# mightywatt.net
KiCad netlist of a schematic drawn in EAGLE
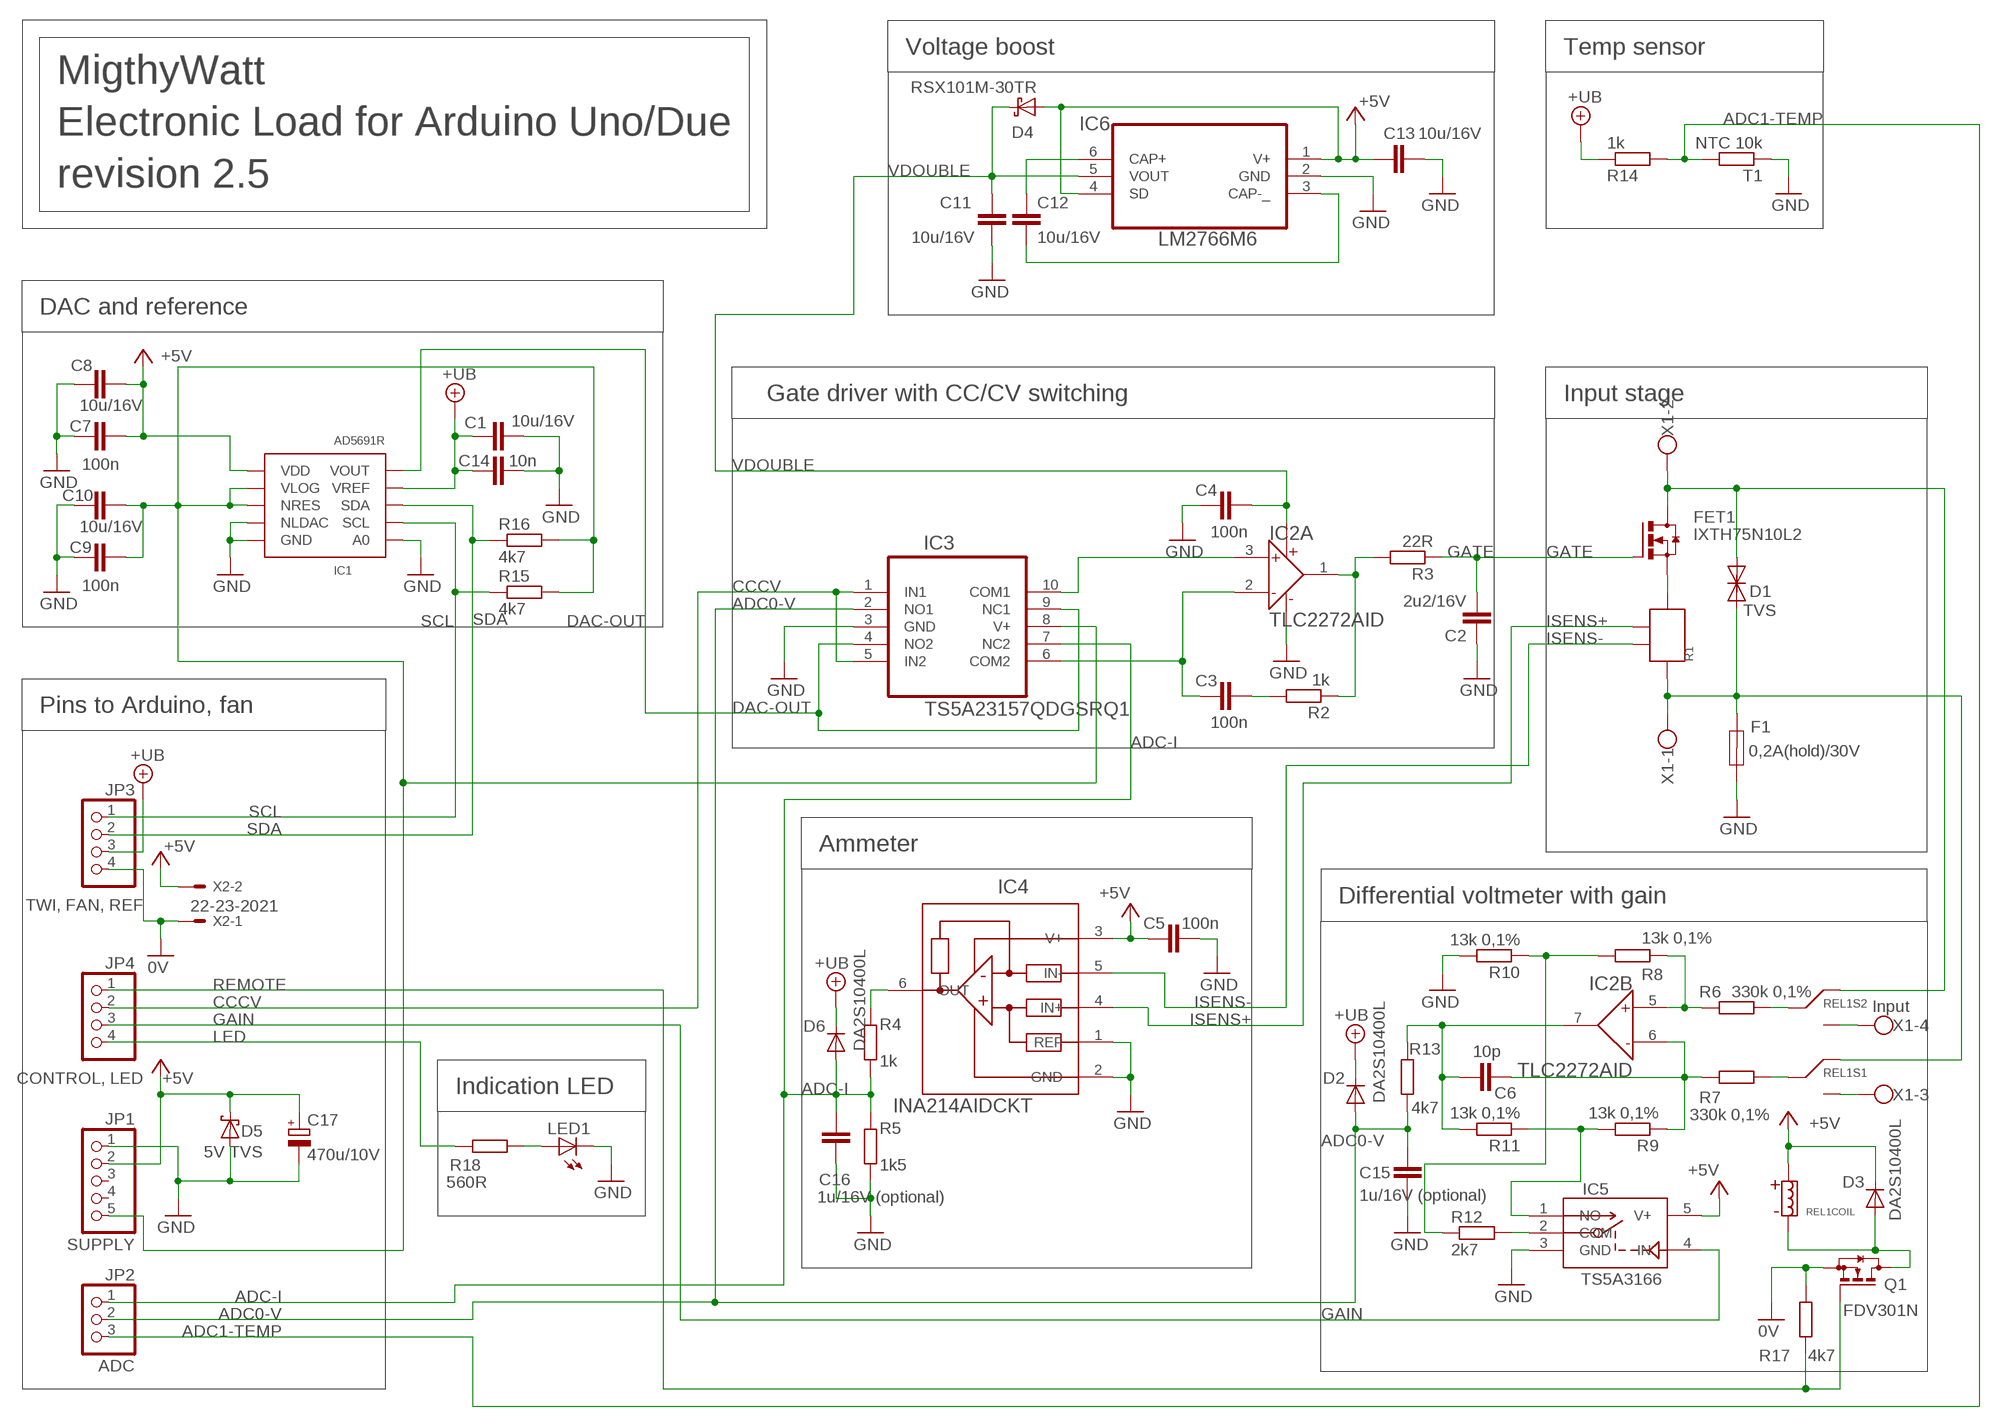
[diagram p0: schematic, sheet 1]

(export (version "E")
  (design (tool "Eeschema 10.0.6"))
  (components
    (comp (ref "C1")
      (value "10u/16V")
      (footprint "eagle-import:C1206")
      (libsource (lib "eagle-import") (part "C-EUC1206"))
    )
    (comp (ref "C2")
      (value "2u2/16V")
      (footprint "eagle-import:C1206")
      (libsource (lib "eagle-import") (part "C-EUC1206"))
    )
    (comp (ref "C3")
      (value "100n")
      (footprint "eagle-import:C0603")
      (libsource (lib "eagle-import") (part "C-EUC0603"))
    )
    (comp (ref "C4")
      (value "100n")
      (footprint "eagle-import:C0603")
      (libsource (lib "eagle-import") (part "C-EUC0603"))
    )
    (comp (ref "C5")
      (value "100n")
      (footprint "eagle-import:C0603")
      (libsource (lib "eagle-import") (part "C-EUC0603"))
    )
    (comp (ref "C6")
      (value "10p")
      (footprint "eagle-import:C0603")
      (libsource (lib "eagle-import") (part "C-EUC0603"))
    )
    (comp (ref "C7")
      (value "100n")
      (footprint "eagle-import:C0603")
      (libsource (lib "eagle-import") (part "C-EUC0603"))
    )
    (comp (ref "C8")
      (value "10u/16V")
      (footprint "eagle-import:C1206")
      (libsource (lib "eagle-import") (part "C-EUC1206"))
    )
    (comp (ref "C9")
      (value "100n")
      (footprint "eagle-import:C0603")
      (libsource (lib "eagle-import") (part "C-EUC0603"))
    )
    (comp (ref "C10")
      (value "10u/16V")
      (footprint "eagle-import:C1206")
      (libsource (lib "eagle-import") (part "C-EUC1206"))
    )
    (comp (ref "C11")
      (value "10u/16V")
      (footprint "eagle-import:C1206")
      (libsource (lib "eagle-import") (part "C-EUC1206"))
    )
    (comp (ref "C12")
      (value "10u/16V")
      (footprint "eagle-import:C1206")
      (libsource (lib "eagle-import") (part "C-EUC1206"))
    )
    (comp (ref "C13")
      (value "10u/16V")
      (footprint "eagle-import:C1206")
      (libsource (lib "eagle-import") (part "C-EUC1206"))
    )
    (comp (ref "C14")
      (value "10n")
      (footprint "eagle-import:C0805")
      (libsource (lib "eagle-import") (part "C-EUC0805"))
    )
    (comp (ref "C15")
      (value "1u/16V (optional)")
      (footprint "eagle-import:C0603")
      (libsource (lib "eagle-import") (part "C-EUC0603"))
    )
    (comp (ref "C16")
      (value "1u/16V (optional)")
      (footprint "eagle-import:C0603")
      (libsource (lib "eagle-import") (part "C-EUC0603"))
    )
    (comp (ref "C17")
      (value "470u/10V")
      (footprint "eagle-import:SMC_E")
      (libsource (lib "eagle-import") (part "CPOL-EUSMCE"))
    )
    (comp (ref "D1")
      (value "TVS")
      (footprint "eagle-import:SMC")
      (libsource (lib "eagle-import") (part "diode-tvs_DIODE-SMC"))
    )
    (comp (ref "D2")
      (value "DA2S10400L")
      (footprint "eagle-import:SOD523")
      (libsource (lib "eagle-import") (part "DIODE-SOD523"))
    )
    (comp (ref "D3")
      (value "DA2S10400L")
      (footprint "eagle-import:SOD523")
      (libsource (lib "eagle-import") (part "DIODE-SOD523"))
    )
    (comp (ref "D4")
      (value "RSX101M-30TR")
      (footprint "eagle-import:SOD123")
      (libsource (lib "eagle-import") (part "diode-schottky_DIODE-SOD123"))
    )
    (comp (ref "D5")
      (value "5V TVS")
      (footprint "eagle-import:SMB")
      (libsource (lib "eagle-import") (part "SCHOTTKY-DIODESMD"))
    )
    (comp (ref "D6")
      (value "DA2S10400L")
      (footprint "eagle-import:SOD523")
      (libsource (lib "eagle-import") (part "DIODE-SOD523"))
    )
    (comp (ref "F1")
      (value "0,2A(hold)/30V")
      (footprint "eagle-import:R1812")
      (fields (field (name "MPN") "1812L050PR"))
      (libsource (lib "eagle-import") (part "LITTELFUSE_1812_500MA"))
    )
    (comp (ref "FET1")
      (value "IXTH75N10L2")
      (footprint "eagle-import:TO-247AD-H")
      (libsource (lib "eagle-import") (part "IXTH75N10L2"))
    )
    (comp (ref "IC1")
      (value "AD5691RAD5691R")
      (footprint "eagle-import:SOP50P490X110-10N")
      (libsource (lib "eagle-import") (part "AD5691RAD5691R"))
    )
    (comp (ref "IC2")
      (value "TLC2272AID")
      (footprint "eagle-import:SOIC127P600X175-8N")
      (libsource (lib "eagle-import") (part "TLC2272AID"))
    )
    (comp (ref "IC3")
      (value "TS5A23157QDGSRQ1")
      (footprint "eagle-import:SOP50P490X110-10N")
      (fields (field (name "MPN") "TS5A23157QDGSRQ1 "))
      (libsource (lib "eagle-import") (part "TS5A23157QDGSRQ1"))
    )
    (comp (ref "IC4")
      (value "INA214AIDCKT")
      (footprint "eagle-import:SOT65P210X110-6N")
      (fields (field (name "MPN") "INA214BIDCKT"))
      (libsource (lib "eagle-import") (part "INA214AIDCKT"))
    )
    (comp (ref "IC5")
      (value "TS5A3166")
      (footprint "eagle-import:SC70-5")
      (libsource (lib "eagle-import") (part "TS5A3166"))
    )
    (comp (ref "IC6")
      (value "LM2766M6")
      (footprint "eagle-import:SOT95P285X122-6N")
      (libsource (lib "eagle-import") (part "LM2766M6"))
    )
    (comp (ref "JP1")
      (value "SUPPLY")
      (footprint "eagle-import:1X05")
      (libsource (lib "eagle-import") (part "PINHD-1X5"))
    )
    (comp (ref "JP2")
      (value "ADC")
      (footprint "eagle-import:1X03")
      (libsource (lib "eagle-import") (part "PINHD-1X3"))
    )
    (comp (ref "JP3")
      (value "TWI, FAN, REF")
      (footprint "eagle-import:1X04")
      (libsource (lib "eagle-import") (part "PINHD-1X4"))
    )
    (comp (ref "JP4")
      (value "CONTROL, LED")
      (footprint "eagle-import:1X04")
      (libsource (lib "eagle-import") (part "PINHD-1X4"))
    )
    (comp (ref "LED1")
      (value "LEDCHIP-LED0805")
      (footprint "eagle-import:CHIP-LED0805")
      (libsource (lib "eagle-import") (part "LEDCHIP-LED0805"))
    )
    (comp (ref "Q1")
      (value "BSS123")
      (footprint "eagle-import:SOT23")
      (fields (field (name "PARTNAME") "FDV301N"))
      (libsource (lib "eagle-import") (part "BSS123"))
    )
    (comp (ref "R1")
      (value "WSL3637")
      (footprint "eagle-import:POWER-R-4TERM")
      (libsource (lib "eagle-import") (part "WSL3637"))
    )
    (comp (ref "R2")
      (value "1k")
      (footprint "eagle-import:R0603")
      (libsource (lib "eagle-import") (part "R-EU_R0603"))
    )
    (comp (ref "R3")
      (value "22R")
      (footprint "eagle-import:R0603")
      (libsource (lib "eagle-import") (part "R-EU_R0603"))
    )
    (comp (ref "R4")
      (value "1k")
      (footprint "eagle-import:R0603")
      (libsource (lib "eagle-import") (part "R-EU_R0603"))
    )
    (comp (ref "R5")
      (value "1k5")
      (footprint "eagle-import:R0603")
      (libsource (lib "eagle-import") (part "R-EU_R0603"))
    )
    (comp (ref "R6")
      (value "330k 0,1%")
      (footprint "eagle-import:R0603")
      (libsource (lib "eagle-import") (part "R-EU_R0603"))
    )
    (comp (ref "R7")
      (value "330k 0,1%")
      (footprint "eagle-import:R0603")
      (libsource (lib "eagle-import") (part "R-EU_R0603"))
    )
    (comp (ref "R8")
      (value "13k 0,1%")
      (footprint "eagle-import:R0603")
      (libsource (lib "eagle-import") (part "R-EU_R0603"))
    )
    (comp (ref "R9")
      (value "13k 0,1%")
      (footprint "eagle-import:R0603")
      (libsource (lib "eagle-import") (part "R-EU_R0603"))
    )
    (comp (ref "R10")
      (value "13k 0,1%")
      (footprint "eagle-import:R0603")
      (libsource (lib "eagle-import") (part "R-EU_R0603"))
    )
    (comp (ref "R11")
      (value "13k 0,1%")
      (footprint "eagle-import:R0603")
      (libsource (lib "eagle-import") (part "R-EU_R0603"))
    )
    (comp (ref "R12")
      (value "2k7")
      (footprint "eagle-import:R0603")
      (libsource (lib "eagle-import") (part "R-EU_R0603"))
    )
    (comp (ref "R13")
      (value "4k7")
      (footprint "eagle-import:R0603")
      (libsource (lib "eagle-import") (part "R-EU_R0603"))
    )
    (comp (ref "R14")
      (value "1k")
      (footprint "eagle-import:R0603")
      (libsource (lib "eagle-import") (part "R-EU_R0603"))
    )
    (comp (ref "R15")
      (value "4k7")
      (footprint "eagle-import:R0603")
      (libsource (lib "eagle-import") (part "R-EU_R0603"))
    )
    (comp (ref "R16")
      (value "4k7")
      (footprint "eagle-import:R0603")
      (libsource (lib "eagle-import") (part "R-EU_R0603"))
    )
    (comp (ref "R17")
      (value "4k7")
      (footprint "eagle-import:R0603")
      (libsource (lib "eagle-import") (part "R-EU_R0603"))
    )
    (comp (ref "R18")
      (value "560R")
      (footprint "eagle-import:R0603")
      (libsource (lib "eagle-import") (part "R-EU_R0603"))
    )
    (comp (ref "REL1")
      (value "IM03NS")
      (footprint "eagle-import:IM03NS-NARROW-RELAY")
      (libsource (lib "eagle-import") (part "IM03NS"))
    )
    (comp (ref "T1")
      (value "NTC 10k")
      (footprint "eagle-import:R0402")
      (libsource (lib "eagle-import") (part "R-EU_R0402"))
    )
    (comp (ref "X1")
      (value "Input")
      (footprint "eagle-import:W237-4")
      (libsource (lib "eagle-import") (part "W237-4"))
    )
    (comp (ref "X2")
      (value "22-23-2021")
      (footprint "eagle-import:22-23-2021")
      (fields (field (name "MF") "MOLEX"))
      (libsource (lib "eagle-import") (part "22-23-2021"))
    )
  )
  (nets
    (net (code "1") (name "+5V") (class "Default")
      (node (ref "C13") (pin "1") (pinfunction "1_1") (pintype "passive"))
      (node (ref "C17") (pin "+") (pinfunction "+_+") (pintype "passive"))
      (node (ref "C5") (pin "1") (pinfunction "1_1") (pintype "passive"))
      (node (ref "C7") (pin "2") (pinfunction "2_2") (pintype "passive"))
      (node (ref "C8") (pin "2") (pinfunction "2_2") (pintype "passive"))
      (node (ref "D3") (pin "C") (pinfunction "C_C") (pintype "passive"))
      (node (ref "D4") (pin "A") (pinfunction "A_A") (pintype "passive"))
      (node (ref "D5") (pin "C") (pinfunction "C_C") (pintype "passive"))
      (node (ref "IC1") (pin "1") (pinfunction "VDD_1") (pintype "bidirectional"))
      (node (ref "IC4") (pin "3") (pinfunction "V+_3") (pintype "power_in"))
      (node (ref "IC5") (pin "5") (pinfunction "V+_5") (pintype "power_in"))
      (node (ref "IC6") (pin "1") (pinfunction "V+_1") (pintype "input"))
      (node (ref "IC6") (pin "4") (pinfunction "SD_4") (pintype "passive"))
      (node (ref "JP1") (pin "2") (pinfunction "2_2") (pintype "passive"))
      (node (ref "REL1") (pin "P$1") (pinfunction "C+_P$1") (pintype "bidirectional"))
      (node (ref "X2") (pin "2") (pinfunction "S_2") (pintype "passive"))
    )
    (net (code "2") (name "+UB") (class "Default")
      (node (ref "C1") (pin "1") (pinfunction "1_1") (pintype "passive"))
      (node (ref "C14") (pin "1") (pinfunction "1_1") (pintype "passive"))
      (node (ref "D2") (pin "C") (pinfunction "C_C") (pintype "passive"))
      (node (ref "D6") (pin "C") (pinfunction "C_C") (pintype "passive"))
      (node (ref "IC1") (pin "9") (pinfunction "VREF_9") (pintype "bidirectional"))
      (node (ref "JP3") (pin "3") (pinfunction "3_3") (pintype "passive"))
      (node (ref "R14") (pin "1") (pinfunction "1_1") (pintype "passive"))
    )
    (net (code "3") (name "/ADC-I") (class "Default")
      (node (ref "C16") (pin "2") (pinfunction "2_2") (pintype "passive"))
      (node (ref "D6") (pin "A") (pinfunction "A_A") (pintype "passive"))
      (node (ref "IC3") (pin "7") (pinfunction "NC2_7") (pintype "passive"))
      (node (ref "JP2") (pin "1") (pinfunction "1_1") (pintype "passive"))
      (node (ref "R4") (pin "2") (pinfunction "2_2") (pintype "passive"))
      (node (ref "R5") (pin "1") (pinfunction "1_1") (pintype "passive"))
    )
    (net (code "4") (name "/ADC0-V") (class "Default")
      (node (ref "C15") (pin "2") (pinfunction "2_2") (pintype "passive"))
      (node (ref "D2") (pin "A") (pinfunction "A_A") (pintype "passive"))
      (node (ref "IC3") (pin "2") (pinfunction "NO1_2") (pintype "passive"))
      (node (ref "JP2") (pin "2") (pinfunction "2_2") (pintype "passive"))
      (node (ref "R13") (pin "1") (pinfunction "1_1") (pintype "passive"))
    )
    (net (code "5") (name "/ADC1-TEMP") (class "Default")
      (node (ref "JP2") (pin "3") (pinfunction "3_3") (pintype "passive"))
      (node (ref "R14") (pin "2") (pinfunction "2_2") (pintype "passive"))
      (node (ref "T1") (pin "2") (pinfunction "2_2") (pintype "passive"))
    )
    (net (code "6") (name "/CCCV") (class "Default")
      (node (ref "IC3") (pin "1") (pinfunction "IN1_1") (pintype "passive"))
      (node (ref "IC3") (pin "5") (pinfunction "IN2_5") (pintype "passive"))
      (node (ref "JP4") (pin "2") (pinfunction "2_2") (pintype "passive"))
    )
    (net (code "7") (name "/DAC-OUT") (class "Default")
      (node (ref "IC1") (pin "10") (pinfunction "VOUT_10") (pintype "bidirectional"))
      (node (ref "IC3") (pin "4") (pinfunction "NO2_4") (pintype "passive"))
      (node (ref "IC3") (pin "9") (pinfunction "NC1_9") (pintype "passive"))
    )
    (net (code "8") (name "/GAIN") (class "Default")
      (node (ref "IC5") (pin "4") (pinfunction "IN_4") (pintype "bidirectional"))
      (node (ref "JP4") (pin "3") (pinfunction "3_3") (pintype "passive"))
    )
    (net (code "9") (name "/GATE") (class "Default")
      (node (ref "C2") (pin "2") (pinfunction "2_2") (pintype "passive"))
      (node (ref "FET1") (pin "G") (pinfunction "G_G") (pintype "passive"))
      (node (ref "R3") (pin "1") (pinfunction "1_1") (pintype "passive"))
    )
    (net (code "10") (name "/ISENS+") (class "Default")
      (node (ref "IC4") (pin "4") (pinfunction "IN+_4") (pintype "input"))
      (node (ref "R1") (pin "SENSE2") (pinfunction "SENSE2_SENSE2") (pintype "bidirectional"))
    )
    (net (code "11") (name "/ISENS-") (class "Default")
      (node (ref "IC4") (pin "5") (pinfunction "IN-_5") (pintype "input"))
      (node (ref "R1") (pin "SENSE1") (pinfunction "SENSE1_SENSE1") (pintype "bidirectional"))
    )
    (net (code "12") (name "/LED") (class "Default")
      (node (ref "JP4") (pin "4") (pinfunction "4_4") (pintype "passive"))
      (node (ref "R18") (pin "1") (pinfunction "1_1") (pintype "passive"))
    )
    (net (code "13") (name "/REMOTE") (class "Default")
      (node (ref "JP4") (pin "1") (pinfunction "1_1") (pintype "passive"))
      (node (ref "Q1") (pin "1") (pinfunction "G_1") (pintype "passive"))
      (node (ref "R17") (pin "2") (pinfunction "2_2") (pintype "passive"))
    )
    (net (code "14") (name "/SCL") (class "Default")
      (node (ref "IC1") (pin "7") (pinfunction "SCL_7") (pintype "bidirectional"))
      (node (ref "JP3") (pin "1") (pinfunction "1_1") (pintype "passive"))
      (node (ref "R15") (pin "1") (pinfunction "1_1") (pintype "passive"))
    )
    (net (code "15") (name "/SDA") (class "Default")
      (node (ref "IC1") (pin "8") (pinfunction "SDA_8") (pintype "bidirectional"))
      (node (ref "JP3") (pin "2") (pinfunction "2_2") (pintype "passive"))
      (node (ref "R16") (pin "1") (pinfunction "1_1") (pintype "passive"))
    )
    (net (code "16") (name "/VDOUBLE") (class "Default")
      (node (ref "C11") (pin "1") (pinfunction "1_1") (pintype "passive"))
      (node (ref "C4") (pin "2") (pinfunction "2_2") (pintype "passive"))
      (node (ref "D4") (pin "C") (pinfunction "C_C") (pintype "passive"))
      (node (ref "IC2") (pin "8") (pinfunction "V+_8") (pintype "power_in"))
      (node (ref "IC6") (pin "5") (pinfunction "VOUT_5") (pintype "output"))
    )
    (net (code "17") (name "0V") (class "Default")
      (node (ref "JP3") (pin "4") (pinfunction "4_4") (pintype "passive"))
      (node (ref "Q1") (pin "2") (pinfunction "S_2") (pintype "passive"))
      (node (ref "R17") (pin "1") (pinfunction "1_1") (pintype "passive"))
      (node (ref "X2") (pin "1") (pinfunction "S_1") (pintype "passive"))
    )
    (net (code "18") (name "GND") (class "Default")
      (node (ref "C1") (pin "2") (pinfunction "2_2") (pintype "passive"))
      (node (ref "C10") (pin "1") (pinfunction "1_1") (pintype "passive"))
      (node (ref "C11") (pin "2") (pinfunction "2_2") (pintype "passive"))
      (node (ref "C13") (pin "2") (pinfunction "2_2") (pintype "passive"))
      (node (ref "C14") (pin "2") (pinfunction "2_2") (pintype "passive"))
      (node (ref "C15") (pin "1") (pinfunction "1_1") (pintype "passive"))
      (node (ref "C16") (pin "1") (pinfunction "1_1") (pintype "passive"))
      (node (ref "C17") (pin "-") (pinfunction "-_-") (pintype "passive"))
      (node (ref "C2") (pin "1") (pinfunction "1_1") (pintype "passive"))
      (node (ref "C4") (pin "1") (pinfunction "1_1") (pintype "passive"))
      (node (ref "C5") (pin "2") (pinfunction "2_2") (pintype "passive"))
      (node (ref "C7") (pin "1") (pinfunction "1_1") (pintype "passive"))
      (node (ref "C8") (pin "1") (pinfunction "1_1") (pintype "passive"))
      (node (ref "C9") (pin "1") (pinfunction "1_1") (pintype "passive"))
      (node (ref "D5") (pin "A") (pinfunction "A_A") (pintype "passive"))
      (node (ref "F1") (pin "2") (pinfunction "P$2_2") (pintype "bidirectional"))
      (node (ref "IC1") (pin "4") (pinfunction "NLDAC_4") (pintype "bidirectional"))
      (node (ref "IC1") (pin "5") (pinfunction "GND_5") (pintype "bidirectional"))
      (node (ref "IC1") (pin "6") (pinfunction "A0_6") (pintype "bidirectional"))
      (node (ref "IC2") (pin "4") (pinfunction "V-/GND_4") (pintype "power_in"))
      (node (ref "IC3") (pin "3") (pinfunction "GND_3") (pintype "passive"))
      (node (ref "IC4") (pin "1") (pinfunction "REF_1") (pintype "input"))
      (node (ref "IC4") (pin "2") (pinfunction "GND_2") (pintype "passive"))
      (node (ref "IC5") (pin "3") (pinfunction "GND_3") (pintype "power_in"))
      (node (ref "IC6") (pin "2") (pinfunction "GND_2") (pintype "passive"))
      (node (ref "JP1") (pin "1") (pinfunction "1_1") (pintype "passive"))
      (node (ref "LED1") (pin "C") (pinfunction "C_C") (pintype "passive"))
      (node (ref "R10") (pin "2") (pinfunction "2_2") (pintype "passive"))
      (node (ref "R5") (pin "2") (pinfunction "2_2") (pintype "passive"))
      (node (ref "T1") (pin "1") (pinfunction "1_1") (pintype "passive"))
    )
    (net (code "19") (name "Net-(C3-Pad2)") (class "Default")
      (node (ref "C3") (pin "2") (pinfunction "2_2") (pintype "passive"))
      (node (ref "R2") (pin "2") (pinfunction "2_2") (pintype "passive"))
    )
    (net (code "20") (name "Net-(F1-P$1)") (class "Default")
      (node (ref "D1") (pin "A") (pinfunction "A_A") (pintype "passive"))
      (node (ref "F1") (pin "1") (pinfunction "P$1_1") (pintype "bidirectional"))
      (node (ref "R1") (pin "POWER1") (pinfunction "POWER1_POWER1") (pintype "bidirectional"))
      (node (ref "REL1") (pin "P$2") (pinfunction "NC_P$2") (pintype "bidirectional"))
      (node (ref "X1") (pin "1") (pinfunction "KL_1") (pintype "passive"))
    )
    (net (code "21") (name "Net-(FET1-PadS)") (class "Default")
      (node (ref "FET1") (pin "S") (pinfunction "S_S") (pintype "passive"))
      (node (ref "R1") (pin "POWER2") (pinfunction "POWER2_POWER2") (pintype "bidirectional"))
    )
    (net (code "22") (name "Net-(IC1-NRES)") (class "Default")
      (node (ref "C10") (pin "2") (pinfunction "2_2") (pintype "passive"))
      (node (ref "C9") (pin "2") (pinfunction "2_2") (pintype "passive"))
      (node (ref "IC1") (pin "2") (pinfunction "VLOG_2") (pintype "bidirectional"))
      (node (ref "IC1") (pin "3") (pinfunction "NRES_3") (pintype "bidirectional"))
      (node (ref "IC3") (pin "8") (pinfunction "V+_8") (pintype "passive"))
      (node (ref "JP1") (pin "5") (pinfunction "5_5") (pintype "passive"))
      (node (ref "R15") (pin "2") (pinfunction "2_2") (pintype "passive"))
      (node (ref "R16") (pin "2") (pinfunction "2_2") (pintype "passive"))
    )
    (net (code "23") (name "Net-(IC2A-IN+)") (class "Default")
      (node (ref "IC2") (pin "3") (pinfunction "IN+_3") (pintype "input"))
      (node (ref "IC3") (pin "10") (pinfunction "COM1_10") (pintype "passive"))
    )
    (net (code "24") (name "Net-(IC2A-IN-)") (class "Default")
      (node (ref "C3") (pin "1") (pinfunction "1_1") (pintype "passive"))
      (node (ref "IC2") (pin "2") (pinfunction "IN-_2") (pintype "input"))
      (node (ref "IC3") (pin "6") (pinfunction "COM2_6") (pintype "passive"))
    )
    (net (code "25") (name "Net-(IC2A-OUT)") (class "Default")
      (node (ref "IC2") (pin "1") (pinfunction "OUT_1") (pintype "output"))
      (node (ref "R2") (pin "1") (pinfunction "1_1") (pintype "passive"))
      (node (ref "R3") (pin "2") (pinfunction "2_2") (pintype "passive"))
    )
    (net (code "26") (name "Net-(IC2B-IN+)") (class "Default")
      (node (ref "IC2") (pin "5") (pinfunction "IN+_5") (pintype "input"))
      (node (ref "R6") (pin "2") (pinfunction "2_2") (pintype "passive"))
      (node (ref "R8") (pin "1") (pinfunction "1_1") (pintype "passive"))
    )
    (net (code "27") (name "Net-(IC2B-IN-)") (class "Default")
      (node (ref "C6") (pin "1") (pinfunction "1_1") (pintype "passive"))
      (node (ref "IC2") (pin "6") (pinfunction "IN-_6") (pintype "input"))
      (node (ref "R7") (pin "2") (pinfunction "2_2") (pintype "passive"))
      (node (ref "R9") (pin "1") (pinfunction "1_1") (pintype "passive"))
    )
    (net (code "28") (name "Net-(IC2B-OUT)") (class "Default")
      (node (ref "C6") (pin "2") (pinfunction "2_2") (pintype "passive"))
      (node (ref "IC2") (pin "7") (pinfunction "OUT_7") (pintype "output"))
      (node (ref "R11") (pin "2") (pinfunction "2_2") (pintype "passive"))
      (node (ref "R13") (pin "2") (pinfunction "2_2") (pintype "passive"))
    )
    (net (code "29") (name "Net-(IC4-OUT)") (class "Default")
      (node (ref "IC4") (pin "6") (pinfunction "OUT_6") (pintype "output"))
      (node (ref "R4") (pin "1") (pinfunction "1_1") (pintype "passive"))
    )
    (net (code "30") (name "Net-(IC5-COM)") (class "Default")
      (node (ref "IC5") (pin "2") (pinfunction "COM_2") (pintype "output"))
      (node (ref "R12") (pin "2") (pinfunction "2_2") (pintype "passive"))
    )
    (net (code "31") (name "Net-(IC5-NO)") (class "Default")
      (node (ref "IC5") (pin "1") (pinfunction "NO_1") (pintype "input"))
      (node (ref "R11") (pin "1") (pinfunction "1_1") (pintype "passive"))
      (node (ref "R9") (pin "2") (pinfunction "2_2") (pintype "passive"))
    )
    (net (code "32") (name "Net-(IC6-CAP+)") (class "Default")
      (node (ref "C12") (pin "1") (pinfunction "1_1") (pintype "passive"))
      (node (ref "IC6") (pin "6") (pinfunction "CAP+_6") (pintype "passive"))
    )
    (net (code "33") (name "Net-(IC6-CAP-_)") (class "Default")
      (node (ref "C12") (pin "2") (pinfunction "2_2") (pintype "passive"))
      (node (ref "IC6") (pin "3") (pinfunction "CAP-__3") (pintype "passive"))
    )
    (net (code "34") (name "Net-(LED1-PadA)") (class "Default")
      (node (ref "LED1") (pin "A") (pinfunction "A_A") (pintype "passive"))
      (node (ref "R18") (pin "2") (pinfunction "2_2") (pintype "passive"))
    )
    (net (code "35") (name "Net-(Q1-D)") (class "Default")
      (node (ref "D3") (pin "A") (pinfunction "A_A") (pintype "passive"))
      (node (ref "Q1") (pin "3") (pinfunction "D_3") (pintype "passive"))
      (node (ref "REL1") (pin "P$8") (pinfunction "C-_P$8") (pintype "bidirectional"))
    )
    (net (code "36") (name "Net-(R10-Pad1)") (class "Default")
      (node (ref "R10") (pin "1") (pinfunction "1_1") (pintype "passive"))
      (node (ref "R12") (pin "1") (pinfunction "1_1") (pintype "passive"))
      (node (ref "R8") (pin "2") (pinfunction "2_2") (pintype "passive"))
    )
    (net (code "37") (name "Net-(REL1B-COM)") (class "Default")
      (node (ref "R7") (pin "1") (pinfunction "1_1") (pintype "passive"))
      (node (ref "REL1") (pin "P$3") (pinfunction "COM_P$3") (pintype "bidirectional"))
    )
    (net (code "38") (name "Net-(REL1B-NO)") (class "Default")
      (node (ref "REL1") (pin "P$4") (pinfunction "NO_P$4") (pintype "bidirectional"))
      (node (ref "X1") (pin "3") (pinfunction "KL_3") (pintype "passive"))
    )
    (net (code "39") (name "Net-(REL1C-COM)") (class "Default")
      (node (ref "R6") (pin "1") (pinfunction "1_1") (pintype "passive"))
      (node (ref "REL1") (pin "P$6") (pinfunction "COM_P$6") (pintype "bidirectional"))
    )
    (net (code "40") (name "Net-(REL1C-NC)") (class "Default")
      (node (ref "D1") (pin "C") (pinfunction "C_C") (pintype "passive"))
      (node (ref "FET1") (pin "D") (pinfunction "D_D") (pintype "passive"))
      (node (ref "REL1") (pin "P$7") (pinfunction "NC_P$7") (pintype "bidirectional"))
      (node (ref "X1") (pin "2") (pinfunction "KL_2") (pintype "passive"))
    )
    (net (code "41") (name "Net-(REL1C-NO)") (class "Default")
      (node (ref "REL1") (pin "P$5") (pinfunction "NO_P$5") (pintype "bidirectional"))
      (node (ref "X1") (pin "4") (pinfunction "KL_4") (pintype "passive"))
    )
    (net (code "42") (name "unconnected-(JP1-Pad3)") (class "Default")
      (node (ref "JP1") (pin "3") (pinfunction "3_3") (pintype "passive"))
    )
    (net (code "43") (name "unconnected-(JP1-Pad4)") (class "Default")
      (node (ref "JP1") (pin "4") (pinfunction "4_4") (pintype "passive"))
    )
  )
)
